# micromouse_v2.net
KiCad netlist of a schematic drawn in EAGLE
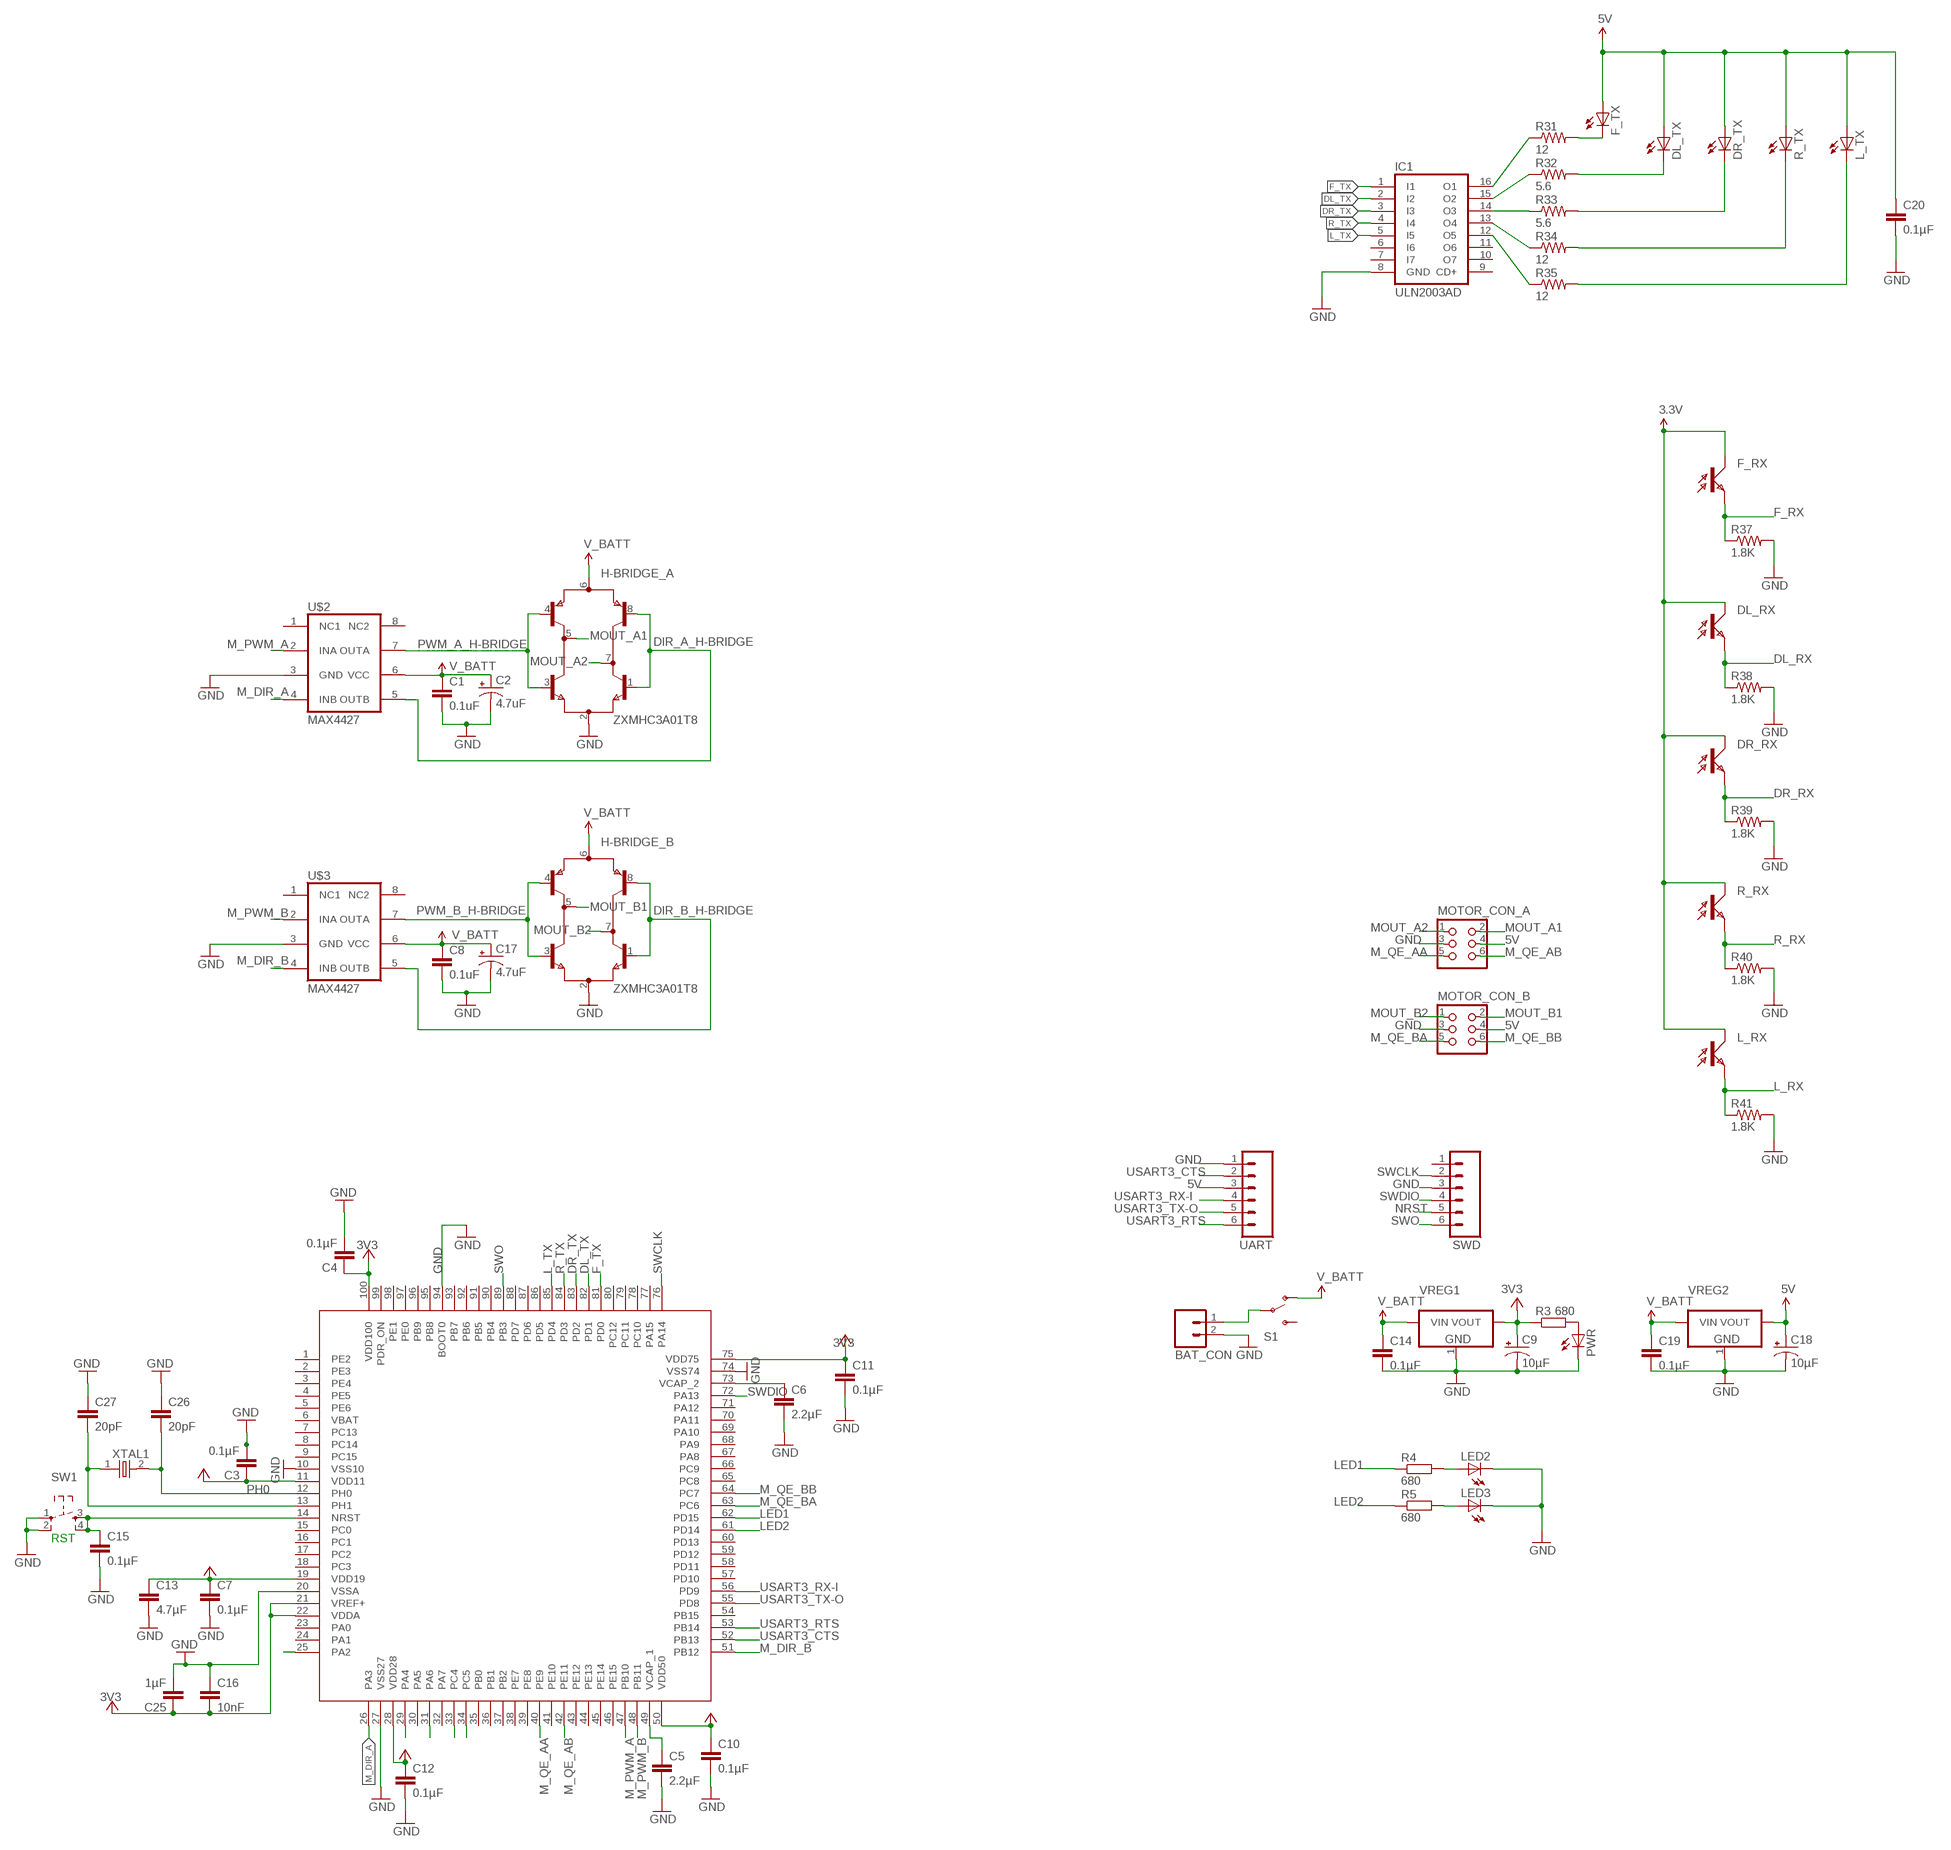
[diagram p0: schematic, sheet 1]

(export (version "E")
  (design (tool "Eeschema 10.0.6"))
  (components
    (comp (ref "BAT_CON")
      (value "M02LOCK_LONGPADS")
      (footprint "eagle-import:1X02_LOCK_LONGPADS")
      (libsource (lib "eagle-import") (part "M02LOCK_LONGPADS"))
    )
    (comp (ref "C1")
      (value "0.1uF")
      (footprint "eagle-import:1206")
      (libsource (lib "eagle-import") (part "CAP1206"))
    )
    (comp (ref "C2")
      (value "4.7uF")
      (footprint "eagle-import:EIA3216-KIT")
      (libsource (lib "eagle-import") (part "CAP_POL1206-KIT"))
    )
    (comp (ref "C3")
      (value "0.1µF")
      (footprint "eagle-import:1206")
      (libsource (lib "eagle-import") (part "CAP1206"))
    )
    (comp (ref "C4")
      (value "0.1µF")
      (footprint "eagle-import:1206")
      (libsource (lib "eagle-import") (part "CAP1206"))
    )
    (comp (ref "C5")
      (value "2.2µF")
      (footprint "eagle-import:1206")
      (libsource (lib "eagle-import") (part "CAP1206"))
    )
    (comp (ref "C6")
      (value "2.2µF")
      (footprint "eagle-import:1206")
      (libsource (lib "eagle-import") (part "CAP1206"))
    )
    (comp (ref "C7")
      (value "0.1µF")
      (footprint "eagle-import:1206")
      (libsource (lib "eagle-import") (part "CAP1206"))
    )
    (comp (ref "C8")
      (value "0.1uF")
      (footprint "eagle-import:1206")
      (libsource (lib "eagle-import") (part "CAP1206"))
    )
    (comp (ref "C9")
      (value "10µF")
      (footprint "eagle-import:EIA3216")
      (libsource (lib "eagle-import") (part "CAP_POL1206"))
    )
    (comp (ref "C10")
      (value "0.1µF")
      (footprint "eagle-import:1206")
      (libsource (lib "eagle-import") (part "CAP1206"))
    )
    (comp (ref "C11")
      (value "0.1µF")
      (footprint "eagle-import:1206")
      (libsource (lib "eagle-import") (part "CAP1206"))
    )
    (comp (ref "C12")
      (value "0.1µF")
      (footprint "eagle-import:1206")
      (libsource (lib "eagle-import") (part "CAP1206"))
    )
    (comp (ref "C13")
      (value "4.7µF")
      (footprint "eagle-import:1206")
      (libsource (lib "eagle-import") (part "CAP1206"))
    )
    (comp (ref "C14")
      (value "0.1µF")
      (footprint "eagle-import:1206")
      (libsource (lib "eagle-import") (part "CAP1206"))
    )
    (comp (ref "C15")
      (value "0.1µF")
      (footprint "eagle-import:1206")
      (libsource (lib "eagle-import") (part "CAP1206"))
    )
    (comp (ref "C16")
      (value "10nF")
      (footprint "eagle-import:1206")
      (libsource (lib "eagle-import") (part "CAP1206"))
    )
    (comp (ref "C17")
      (value "4.7uF")
      (footprint "eagle-import:EIA3216-KIT")
      (libsource (lib "eagle-import") (part "CAP_POL1206-KIT"))
    )
    (comp (ref "C18")
      (value "10µF")
      (footprint "eagle-import:EIA3216")
      (libsource (lib "eagle-import") (part "CAP_POL1206"))
    )
    (comp (ref "C19")
      (value "0.1µF")
      (footprint "eagle-import:1206")
      (libsource (lib "eagle-import") (part "CAP1206"))
    )
    (comp (ref "C20")
      (value "0.1µF")
      (footprint "eagle-import:1206")
      (libsource (lib "eagle-import") (part "CAP1206"))
    )
    (comp (ref "C25")
      (value "1µF")
      (footprint "eagle-import:1206")
      (libsource (lib "eagle-import") (part "CAP1206"))
    )
    (comp (ref "C26")
      (value "20pF")
      (footprint "eagle-import:1206")
      (libsource (lib "eagle-import") (part "CAP1206"))
    )
    (comp (ref "C27")
      (value "20pF")
      (footprint "eagle-import:1206")
      (libsource (lib "eagle-import") (part "CAP1206"))
    )
    (comp (ref "DL_RX")
      (value "BPX81")
      (footprint "eagle-import:BPX81")
      (libsource (lib "eagle-import") (part "BPX81"))
    )
    (comp (ref "DL_TX")
      (value "SFH482")
      (footprint "eagle-import:SFH482")
      (libsource (lib "eagle-import") (part "SFH482"))
    )
    (comp (ref "DR_RX")
      (value "BPX81")
      (footprint "eagle-import:BPX81")
      (libsource (lib "eagle-import") (part "BPX81"))
    )
    (comp (ref "DR_TX")
      (value "SFH482")
      (footprint "eagle-import:SFH482")
      (libsource (lib "eagle-import") (part "SFH482"))
    )
    (comp (ref "F_RX")
      (value "BPX81")
      (footprint "eagle-import:BPX81")
      (libsource (lib "eagle-import") (part "BPX81"))
    )
    (comp (ref "F_TX")
      (value "SFH482")
      (footprint "eagle-import:SFH482")
      (libsource (lib "eagle-import") (part "SFH482"))
    )
    (comp (ref "H-BRIDGE_A")
      (value "ZXMHC3A01T8")
      (footprint "eagle-import:SM8")
      (libsource (lib "eagle-import") (part "H-BRIDGE"))
    )
    (comp (ref "H-BRIDGE_B")
      (value "ZXMHC3A01T8")
      (footprint "eagle-import:SM8")
      (libsource (lib "eagle-import") (part "H-BRIDGE"))
    )
    (comp (ref "IC1")
      (value "ULN2003AD")
      (footprint "eagle-import:SO16")
      (libsource (lib "eagle-import") (part "ULN2003AD"))
    )
    (comp (ref "LED2")
      (value "LED-FKIT-1206")
      (footprint "eagle-import:FKIT-LED-1206")
      (libsource (lib "eagle-import") (part "LED-FKIT-1206"))
    )
    (comp (ref "LED3")
      (value "LED-FKIT-1206")
      (footprint "eagle-import:FKIT-LED-1206")
      (libsource (lib "eagle-import") (part "LED-FKIT-1206"))
    )
    (comp (ref "L_RX")
      (value "BPX81")
      (footprint "eagle-import:BPX81")
      (libsource (lib "eagle-import") (part "BPX81"))
    )
    (comp (ref "L_TX")
      (value "SFH482")
      (footprint "eagle-import:SFH482")
      (libsource (lib "eagle-import") (part "SFH482"))
    )
    (comp (ref "MOTOR_CON_A")
      (value "CON_HEADER_2X03-PTH")
      (footprint "eagle-import:M2X3")
      (libsource (lib "eagle-import") (part "CON_HEADER_2X03-PTH"))
    )
    (comp (ref "MOTOR_CON_B")
      (value "CON_HEADER_2X03-PTH")
      (footprint "eagle-import:M2X3")
      (libsource (lib "eagle-import") (part "CON_HEADER_2X03-PTH"))
    )
    (comp (ref "PWR")
      (value "LED-FKIT-1206")
      (footprint "eagle-import:FKIT-LED-1206")
      (libsource (lib "eagle-import") (part "LED-FKIT-1206"))
    )
    (comp (ref "R3")
      (value "680")
      (footprint "eagle-import:R1206")
      (libsource (lib "eagle-import") (part "RESISTOR-1206"))
    )
    (comp (ref "R4")
      (value "680")
      (footprint "eagle-import:R1206")
      (libsource (lib "eagle-import") (part "RESISTOR-1206"))
    )
    (comp (ref "R5")
      (value "680")
      (footprint "eagle-import:R1206")
      (libsource (lib "eagle-import") (part "RESISTOR-1206"))
    )
    (comp (ref "R31")
      (value "12")
      (footprint "eagle-import:1206")
      (libsource (lib "eagle-import") (part "RESISTOR1206"))
    )
    (comp (ref "R32")
      (value "5.6")
      (footprint "eagle-import:1206")
      (libsource (lib "eagle-import") (part "RESISTOR1206"))
    )
    (comp (ref "R33")
      (value "5.6")
      (footprint "eagle-import:1206")
      (libsource (lib "eagle-import") (part "RESISTOR1206"))
    )
    (comp (ref "R34")
      (value "12")
      (footprint "eagle-import:1206")
      (libsource (lib "eagle-import") (part "RESISTOR1206"))
    )
    (comp (ref "R35")
      (value "12")
      (footprint "eagle-import:1206")
      (libsource (lib "eagle-import") (part "RESISTOR1206"))
    )
    (comp (ref "R37")
      (value "1.8K")
      (footprint "eagle-import:1206")
      (libsource (lib "eagle-import") (part "RESISTOR1206"))
    )
    (comp (ref "R38")
      (value "1.8K")
      (footprint "eagle-import:1206")
      (libsource (lib "eagle-import") (part "RESISTOR1206"))
    )
    (comp (ref "R39")
      (value "1.8K")
      (footprint "eagle-import:1206")
      (libsource (lib "eagle-import") (part "RESISTOR1206"))
    )
    (comp (ref "R40")
      (value "1.8K")
      (footprint "eagle-import:1206")
      (libsource (lib "eagle-import") (part "RESISTOR1206"))
    )
    (comp (ref "R41")
      (value "1.8K")
      (footprint "eagle-import:1206")
      (libsource (lib "eagle-import") (part "RESISTOR1206"))
    )
    (comp (ref "R_RX")
      (value "BPX81")
      (footprint "eagle-import:BPX81")
      (libsource (lib "eagle-import") (part "BPX81"))
    )
    (comp (ref "R_TX")
      (value "SFH482")
      (footprint "eagle-import:SFH482")
      (libsource (lib "eagle-import") (part "SFH482"))
    )
    (comp (ref "S1")
      (value "SWITCH-SPDTPTH")
      (footprint "eagle-import:SWITCH-SPDT")
      (libsource (lib "eagle-import") (part "SWITCH-SPDTPTH"))
    )
    (comp (ref "SW1")
      (value "SW_TACT_4P")
      (footprint "eagle-import:SW_TACT_SMALL")
      (libsource (lib "eagle-import") (part "SW_TACT_4P"))
    )
    (comp (ref "SWD")
      (value "M06LOCK")
      (footprint "eagle-import:1X06_LOCK")
      (libsource (lib "eagle-import") (part "M06LOCK"))
    )
    (comp (ref "U$1")
      (value "STM32F40X_QFP_PACKAGE")
      (footprint "eagle-import:TQFP-100-14X14MM")
      (libsource (lib "eagle-import") (part "STM32F40X_QFP_PACKAGE"))
    )
    (comp (ref "U$2")
      (value "MAX4427")
      (footprint "eagle-import:SO08")
      (libsource (lib "eagle-import") (part "MAX4427"))
    )
    (comp (ref "U$3")
      (value "MAX4427")
      (footprint "eagle-import:SO08")
      (libsource (lib "eagle-import") (part "MAX4427"))
    )
    (comp (ref "UART")
      (value "M06LOCK")
      (footprint "eagle-import:1X06_LOCK")
      (libsource (lib "eagle-import") (part "M06LOCK"))
    )
    (comp (ref "VREG1")
      (value "VREG_3PINS-SOT-223")
      (footprint "eagle-import:SOT-223")
      (libsource (lib "eagle-import") (part "VREG_3PINS-SOT-223"))
    )
    (comp (ref "VREG2")
      (value "VREG_3PINS-SOT-223")
      (footprint "eagle-import:SOT-223")
      (libsource (lib "eagle-import") (part "VREG_3PINS-SOT-223"))
    )
    (comp (ref "XTAL1")
      (value "OSC-XTAL-HC-49U-SMD")
      (footprint "eagle-import:HC-49U")
      (libsource (lib "eagle-import") (part "OSC-XTAL-HC-49U-SMD"))
    )
  )
  (nets
    (net (code "1") (name "/DIR_A_H-BRIDGE") (class "Default")
      (node (ref "H-BRIDGE_A") (pin "1") (pinfunction "B3_1") (pintype "passive"))
      (node (ref "H-BRIDGE_A") (pin "8") (pinfunction "B4_8") (pintype "passive"))
      (node (ref "U$2") (pin "5") (pinfunction "OUTB_5") (pintype "power_in"))
    )
    (net (code "2") (name "/DIR_B_H-BRIDGE") (class "Default")
      (node (ref "H-BRIDGE_B") (pin "1") (pinfunction "B3_1") (pintype "passive"))
      (node (ref "H-BRIDGE_B") (pin "8") (pinfunction "B4_8") (pintype "passive"))
      (node (ref "U$3") (pin "5") (pinfunction "OUTB_5") (pintype "power_in"))
    )
    (net (code "3") (name "/DL_RX") (class "Default")
      (node (ref "DL_RX") (pin "E") (pinfunction "E_E") (pintype "passive"))
      (node (ref "R38") (pin "1") (pinfunction "1_1") (pintype "passive"))
      (node (ref "U$1") (pin "29") (pinfunction "PA4_29") (pintype "bidirectional"))
    )
    (net (code "4") (name "/DR_RX") (class "Default")
      (node (ref "DR_RX") (pin "E") (pinfunction "E_E") (pintype "passive"))
      (node (ref "R39") (pin "1") (pinfunction "1_1") (pintype "passive"))
      (node (ref "U$1") (pin "33") (pinfunction "PC4_33") (pintype "bidirectional"))
    )
    (net (code "5") (name "/F_RX") (class "Default")
      (node (ref "F_RX") (pin "E") (pinfunction "E_E") (pintype "passive"))
      (node (ref "R37") (pin "1") (pinfunction "1_1") (pintype "passive"))
      (node (ref "U$1") (pin "31") (pinfunction "PA6_31") (pintype "bidirectional"))
    )
    (net (code "6") (name "/LED1") (class "Default")
      (node (ref "R4") (pin "1") (pinfunction "1_1") (pintype "passive"))
      (node (ref "U$1") (pin "62") (pinfunction "PD15_62") (pintype "bidirectional"))
    )
    (net (code "7") (name "/LED2") (class "Default")
      (node (ref "R5") (pin "1") (pinfunction "1_1") (pintype "passive"))
      (node (ref "U$1") (pin "61") (pinfunction "PD14_61") (pintype "bidirectional"))
    )
    (net (code "8") (name "/L_RX") (class "Default")
      (node (ref "L_RX") (pin "E") (pinfunction "E_E") (pintype "passive"))
      (node (ref "R41") (pin "1") (pinfunction "1_1") (pintype "passive"))
      (node (ref "U$1") (pin "25") (pinfunction "PA2_25") (pintype "bidirectional"))
    )
    (net (code "9") (name "/MOUT_A1") (class "Default")
      (node (ref "H-BRIDGE_A") (pin "5") (pinfunction "C1C2_5") (pintype "passive"))
      (node (ref "MOTOR_CON_A") (pin "2") (pinfunction "2_2") (pintype "passive"))
    )
    (net (code "10") (name "/MOUT_A2") (class "Default")
      (node (ref "H-BRIDGE_A") (pin "7") (pinfunction "C3C4_7") (pintype "passive"))
      (node (ref "MOTOR_CON_A") (pin "1") (pinfunction "1_1") (pintype "passive"))
    )
    (net (code "11") (name "/MOUT_B1") (class "Default")
      (node (ref "H-BRIDGE_B") (pin "5") (pinfunction "C1C2_5") (pintype "passive"))
      (node (ref "MOTOR_CON_B") (pin "2") (pinfunction "2_2") (pintype "passive"))
    )
    (net (code "12") (name "/MOUT_B2") (class "Default")
      (node (ref "H-BRIDGE_B") (pin "7") (pinfunction "C3C4_7") (pintype "passive"))
      (node (ref "MOTOR_CON_B") (pin "1") (pinfunction "1_1") (pintype "passive"))
    )
    (net (code "13") (name "/M_DIR_B") (class "Default")
      (node (ref "U$1") (pin "51") (pinfunction "PB12_51") (pintype "bidirectional"))
      (node (ref "U$3") (pin "4") (pinfunction "INB_4") (pintype "passive"))
    )
    (net (code "14") (name "/M_PWM_A") (class "Default")
      (node (ref "U$1") (pin "47") (pinfunction "PB10_47") (pintype "bidirectional"))
      (node (ref "U$2") (pin "2") (pinfunction "INA_2") (pintype "passive"))
    )
    (net (code "15") (name "/M_PWM_B") (class "Default")
      (node (ref "U$1") (pin "48") (pinfunction "PB11_48") (pintype "bidirectional"))
      (node (ref "U$3") (pin "2") (pinfunction "INA_2") (pintype "passive"))
    )
    (net (code "16") (name "/M_QE_AA") (class "Default")
      (node (ref "MOTOR_CON_A") (pin "5") (pinfunction "5_5") (pintype "passive"))
      (node (ref "U$1") (pin "40") (pinfunction "PE9_40") (pintype "bidirectional"))
    )
    (net (code "17") (name "/M_QE_AB") (class "Default")
      (node (ref "MOTOR_CON_A") (pin "6") (pinfunction "6_6") (pintype "passive"))
      (node (ref "U$1") (pin "42") (pinfunction "PE11_42") (pintype "bidirectional"))
    )
    (net (code "18") (name "/M_QE_BA") (class "Default")
      (node (ref "MOTOR_CON_B") (pin "5") (pinfunction "5_5") (pintype "passive"))
      (node (ref "U$1") (pin "63") (pinfunction "PC6_63") (pintype "bidirectional"))
    )
    (net (code "19") (name "/M_QE_BB") (class "Default")
      (node (ref "MOTOR_CON_B") (pin "6") (pinfunction "6_6") (pintype "passive"))
      (node (ref "U$1") (pin "64") (pinfunction "PC7_64") (pintype "bidirectional"))
    )
    (net (code "20") (name "/NRST") (class "Default")
      (node (ref "C15") (pin "1") (pinfunction "1_1") (pintype "passive"))
      (node (ref "SW1") (pin "3") (pinfunction "3_3") (pintype "passive"))
      (node (ref "SW1") (pin "4") (pinfunction "4_4") (pintype "passive"))
      (node (ref "SWD") (pin "5") (pinfunction "5_5") (pintype "passive"))
      (node (ref "U$1") (pin "14") (pinfunction "NRST_14") (pintype "bidirectional"))
    )
    (net (code "21") (name "/PH0") (class "Default")
      (node (ref "C26") (pin "2") (pinfunction "2_2") (pintype "passive"))
      (node (ref "U$1") (pin "12") (pinfunction "PH0_12") (pintype "bidirectional"))
      (node (ref "XTAL1") (pin "2") (pinfunction "2_2") (pintype "passive"))
    )
    (net (code "22") (name "/PWM_A_H-BRIDGE") (class "Default")
      (node (ref "H-BRIDGE_A") (pin "3") (pinfunction "B2_3") (pintype "passive"))
      (node (ref "H-BRIDGE_A") (pin "4") (pinfunction "B1_4") (pintype "passive"))
      (node (ref "U$2") (pin "7") (pinfunction "OUTA_7") (pintype "output"))
    )
    (net (code "23") (name "/PWM_B_H-BRIDGE") (class "Default")
      (node (ref "H-BRIDGE_B") (pin "3") (pinfunction "B2_3") (pintype "passive"))
      (node (ref "H-BRIDGE_B") (pin "4") (pinfunction "B1_4") (pintype "passive"))
      (node (ref "U$3") (pin "7") (pinfunction "OUTA_7") (pintype "output"))
    )
    (net (code "24") (name "/R_RX") (class "Default")
      (node (ref "R40") (pin "1") (pinfunction "1_1") (pintype "passive"))
      (node (ref "R_RX") (pin "E") (pinfunction "E_E") (pintype "passive"))
      (node (ref "U$1") (pin "34") (pinfunction "PC5_34") (pintype "bidirectional"))
    )
    (net (code "25") (name "/SWCLK") (class "Default")
      (node (ref "SWD") (pin "2") (pinfunction "2_2") (pintype "passive"))
      (node (ref "U$1") (pin "76") (pinfunction "PA14_76") (pintype "bidirectional"))
    )
    (net (code "26") (name "/SWDIO") (class "Default")
      (node (ref "SWD") (pin "4") (pinfunction "4_4") (pintype "passive"))
      (node (ref "U$1") (pin "72") (pinfunction "PA13_72") (pintype "bidirectional"))
    )
    (net (code "27") (name "/SWO") (class "Default")
      (node (ref "SWD") (pin "6") (pinfunction "6_6") (pintype "passive"))
      (node (ref "U$1") (pin "89") (pinfunction "PB3_89") (pintype "bidirectional"))
    )
    (net (code "28") (name "/USART3_CTS") (class "Default")
      (node (ref "U$1") (pin "52") (pinfunction "PB13_52") (pintype "bidirectional"))
      (node (ref "UART") (pin "2") (pinfunction "2_2") (pintype "passive"))
    )
    (net (code "29") (name "/USART3_RTS") (class "Default")
      (node (ref "U$1") (pin "53") (pinfunction "PB14_53") (pintype "bidirectional"))
      (node (ref "UART") (pin "6") (pinfunction "6_6") (pintype "passive"))
    )
    (net (code "30") (name "/USART3_RX-I") (class "Default")
      (node (ref "U$1") (pin "56") (pinfunction "PD9_56") (pintype "bidirectional"))
      (node (ref "UART") (pin "4") (pinfunction "4_4") (pintype "passive"))
    )
    (net (code "31") (name "/USART3_TX-O") (class "Default")
      (node (ref "U$1") (pin "55") (pinfunction "PD8_55") (pintype "bidirectional"))
      (node (ref "UART") (pin "5") (pinfunction "5_5") (pintype "passive"))
    )
    (net (code "32") (name "3.3V") (class "Default")
      (node (ref "DL_RX") (pin "C") (pinfunction "C_C") (pintype "passive"))
      (node (ref "DR_RX") (pin "C") (pinfunction "C_C") (pintype "passive"))
      (node (ref "F_RX") (pin "C") (pinfunction "C_C") (pintype "passive"))
      (node (ref "L_RX") (pin "C") (pinfunction "C_C") (pintype "passive"))
      (node (ref "R_RX") (pin "C") (pinfunction "C_C") (pintype "passive"))
    )
    (net (code "33") (name "5V") (class "Default")
      (node (ref "C18") (pin "A") (pinfunction "+_A") (pintype "passive"))
      (node (ref "C20") (pin "1") (pinfunction "1_1") (pintype "passive"))
      (node (ref "DL_TX") (pin "A") (pinfunction "A_A") (pintype "passive"))
      (node (ref "DR_TX") (pin "A") (pinfunction "A_A") (pintype "passive"))
      (node (ref "F_TX") (pin "A") (pinfunction "A_A") (pintype "passive"))
      (node (ref "L_TX") (pin "A") (pinfunction "A_A") (pintype "passive"))
      (node (ref "MOTOR_CON_A") (pin "4") (pinfunction "4_4") (pintype "passive"))
      (node (ref "MOTOR_CON_B") (pin "4") (pinfunction "4_4") (pintype "passive"))
      (node (ref "R_TX") (pin "A") (pinfunction "A_A") (pintype "passive"))
      (node (ref "UART") (pin "3") (pinfunction "3_3") (pintype "passive"))
      (node (ref "VREG2") (pin "2") (pinfunction "VOUT_2") (pintype "bidirectional"))
    )
    (net (code "34") (name "DL_TX") (class "Default")
      (node (ref "IC1") (pin "2") (pinfunction "I2_2") (pintype "input"))
      (node (ref "U$1") (pin "82") (pinfunction "PD1_82") (pintype "bidirectional"))
    )
    (net (code "35") (name "DR_TX") (class "Default")
      (node (ref "IC1") (pin "3") (pinfunction "I3_3") (pintype "input"))
      (node (ref "U$1") (pin "83") (pinfunction "PD2_83") (pintype "bidirectional"))
    )
    (net (code "36") (name "F_TX") (class "Default")
      (node (ref "IC1") (pin "1") (pinfunction "I1_1") (pintype "input"))
      (node (ref "U$1") (pin "81") (pinfunction "PD0_81") (pintype "bidirectional"))
    )
    (net (code "37") (name "GND") (class "Default")
      (node (ref "BAT_CON") (pin "2") (pinfunction "2_2") (pintype "passive"))
      (node (ref "C1") (pin "2") (pinfunction "2_2") (pintype "passive"))
      (node (ref "C10") (pin "2") (pinfunction "2_2") (pintype "passive"))
      (node (ref "C11") (pin "2") (pinfunction "2_2") (pintype "passive"))
      (node (ref "C12") (pin "2") (pinfunction "2_2") (pintype "passive"))
      (node (ref "C13") (pin "2") (pinfunction "2_2") (pintype "passive"))
      (node (ref "C14") (pin "2") (pinfunction "2_2") (pintype "passive"))
      (node (ref "C15") (pin "2") (pinfunction "2_2") (pintype "passive"))
      (node (ref "C16") (pin "1") (pinfunction "1_1") (pintype "passive"))
      (node (ref "C17") (pin "C") (pinfunction "-_C") (pintype "passive"))
      (node (ref "C18") (pin "C") (pinfunction "-_C") (pintype "passive"))
      (node (ref "C19") (pin "2") (pinfunction "2_2") (pintype "passive"))
      (node (ref "C2") (pin "C") (pinfunction "-_C") (pintype "passive"))
      (node (ref "C20") (pin "2") (pinfunction "2_2") (pintype "passive"))
      (node (ref "C25") (pin "2") (pinfunction "2_2") (pintype "passive"))
      (node (ref "C26") (pin "1") (pinfunction "1_1") (pintype "passive"))
      (node (ref "C27") (pin "1") (pinfunction "1_1") (pintype "passive"))
      (node (ref "C3") (pin "2") (pinfunction "2_2") (pintype "passive"))
      (node (ref "C4") (pin "2") (pinfunction "2_2") (pintype "passive"))
      (node (ref "C5") (pin "2") (pinfunction "2_2") (pintype "passive"))
      (node (ref "C6") (pin "2") (pinfunction "2_2") (pintype "passive"))
      (node (ref "C7") (pin "2") (pinfunction "2_2") (pintype "passive"))
      (node (ref "C8") (pin "2") (pinfunction "2_2") (pintype "passive"))
      (node (ref "C9") (pin "C") (pinfunction "-_C") (pintype "passive"))
      (node (ref "H-BRIDGE_A") (pin "2") (pinfunction "E2E3_2") (pintype "passive"))
      (node (ref "H-BRIDGE_B") (pin "2") (pinfunction "E2E3_2") (pintype "passive"))
      (node (ref "IC1") (pin "8") (pinfunction "GND_8") (pintype "power_in"))
      (node (ref "LED2") (pin "C") (pinfunction "C_C") (pintype "passive"))
      (node (ref "LED3") (pin "C") (pinfunction "C_C") (pintype "passive"))
      (node (ref "MOTOR_CON_A") (pin "3") (pinfunction "3_3") (pintype "passive"))
      (node (ref "MOTOR_CON_B") (pin "3") (pinfunction "3_3") (pintype "passive"))
      (node (ref "PWR") (pin "C") (pinfunction "C_C") (pintype "passive"))
      (node (ref "R37") (pin "2") (pinfunction "2_2") (pintype "passive"))
      (node (ref "R38") (pin "2") (pinfunction "2_2") (pintype "passive"))
      (node (ref "R39") (pin "2") (pinfunction "2_2") (pintype "passive"))
      (node (ref "R40") (pin "2") (pinfunction "2_2") (pintype "passive"))
      (node (ref "R41") (pin "2") (pinfunction "2_2") (pintype "passive"))
      (node (ref "SW1") (pin "1") (pinfunction "1_1") (pintype "passive"))
      (node (ref "SW1") (pin "2") (pinfunction "2_2") (pintype "passive"))
      (node (ref "SWD") (pin "3") (pinfunction "3_3") (pintype "passive"))
      (node (ref "U$1") (pin "10") (pinfunction "VSS10_10") (pintype "bidirectional"))
      (node (ref "U$1") (pin "20") (pinfunction "VSSA_20") (pintype "bidirectional"))
      (node (ref "U$1") (pin "27") (pinfunction "VSS27_27") (pintype "bidirectional"))
      (node (ref "U$1") (pin "74") (pinfunction "VSS74_74") (pintype "bidirectional"))
      (node (ref "U$1") (pin "94") (pinfunction "BOOT0_94") (pintype "bidirectional"))
      (node (ref "U$2") (pin "3") (pinfunction "GND_3") (pintype "passive"))
      (node (ref "U$3") (pin "3") (pinfunction "GND_3") (pintype "passive"))
      (node (ref "UART") (pin "1") (pinfunction "1_1") (pintype "passive"))
      (node (ref "VREG1") (pin "1") (pinfunction "GND_1") (pintype "bidirectional"))
      (node (ref "VREG2") (pin "1") (pinfunction "GND_1") (pintype "bidirectional"))
    )
    (net (code "38") (name "L_TX") (class "Default")
      (node (ref "IC1") (pin "5") (pinfunction "I5_5") (pintype "input"))
      (node (ref "U$1") (pin "85") (pinfunction "PD4_85") (pintype "bidirectional"))
    )
    (net (code "39") (name "M_DIR_A") (class "Default")
      (node (ref "U$1") (pin "26") (pinfunction "PA3_26") (pintype "bidirectional"))
      (node (ref "U$2") (pin "4") (pinfunction "INB_4") (pintype "passive"))
    )
    (net (code "40") (name "Net-(DL_TX-C)") (class "Default")
      (node (ref "DL_TX") (pin "K") (pinfunction "C_K") (pintype "passive"))
      (node (ref "R32") (pin "2") (pinfunction "2_2") (pintype "passive"))
    )
    (net (code "41") (name "Net-(DR_TX-C)") (class "Default")
      (node (ref "DR_TX") (pin "K") (pinfunction "C_K") (pintype "passive"))
      (node (ref "R33") (pin "2") (pinfunction "2_2") (pintype "passive"))
    )
    (net (code "42") (name "Net-(F_TX-C)") (class "Default")
      (node (ref "F_TX") (pin "K") (pinfunction "C_K") (pintype "passive"))
      (node (ref "R31") (pin "2") (pinfunction "2_2") (pintype "passive"))
    )
    (net (code "43") (name "Net-(IC1-O1)") (class "Default")
      (node (ref "IC1") (pin "16") (pinfunction "O1_16") (pintype "open_collector"))
      (node (ref "R31") (pin "1") (pinfunction "1_1") (pintype "passive"))
    )
    (net (code "44") (name "Net-(IC1-O2)") (class "Default")
      (node (ref "IC1") (pin "15") (pinfunction "O2_15") (pintype "open_collector"))
      (node (ref "R32") (pin "1") (pinfunction "1_1") (pintype "passive"))
    )
    (net (code "45") (name "Net-(IC1-O3)") (class "Default")
      (node (ref "IC1") (pin "14") (pinfunction "O3_14") (pintype "open_collector"))
      (node (ref "R33") (pin "1") (pinfunction "1_1") (pintype "passive"))
    )
    (net (code "46") (name "Net-(IC1-O4)") (class "Default")
      (node (ref "IC1") (pin "13") (pinfunction "O4_13") (pintype "open_collector"))
      (node (ref "R34") (pin "1") (pinfunction "1_1") (pintype "passive"))
    )
    (net (code "47") (name "Net-(IC1-O5)") (class "Default")
      (node (ref "IC1") (pin "12") (pinfunction "O5_12") (pintype "open_collector"))
      (node (ref "R35") (pin "1") (pinfunction "1_1") (pintype "passive"))
    )
    (net (code "48") (name "Net-(LED2-PadA)") (class "Default")
      (node (ref "LED2") (pin "A") (pinfunction "A_A") (pintype "passive"))
      (node (ref "R4") (pin "2") (pinfunction "2_2") (pintype "passive"))
    )
    (net (code "49") (name "Net-(LED3-PadA)") (class "Default")
      (node (ref "LED3") (pin "A") (pinfunction "A_A") (pintype "passive"))
      (node (ref "R5") (pin "2") (pinfunction "2_2") (pintype "passive"))
    )
    (net (code "50") (name "Net-(L_TX-C)") (class "Default")
      (node (ref "L_TX") (pin "K") (pinfunction "C_K") (pintype "passive"))
      (node (ref "R35") (pin "2") (pinfunction "2_2") (pintype "passive"))
    )
    (net (code "51") (name "Net-(PWR-PadA)") (class "Default")
      (node (ref "PWR") (pin "A") (pinfunction "A_A") (pintype "passive"))
      (node (ref "R3") (pin "2") (pinfunction "2_2") (pintype "passive"))
    )
    (net (code "52") (name "Net-(R_TX-C)") (class "Default")
      (node (ref "R34") (pin "2") (pinfunction "2_2") (pintype "passive"))
      (node (ref "R_TX") (pin "K") (pinfunction "C_K") (pintype "passive"))
    )
    (net (code "53") (name "Net-(S1-P)") (class "Default")
      (node (ref "BAT_CON") (pin "1") (pinfunction "1_1") (pintype "passive"))
      (node (ref "S1") (pin "2") (pinfunction "P_2") (pintype "passive"))
    )
    (net (code "54") (name "Net-(U$1-PH1)") (class "Default")
      (node (ref "C27") (pin "2") (pinfunction "2_2") (pintype "passive"))
      (node (ref "U$1") (pin "13") (pinfunction "PH1_13") (pintype "bidirectional"))
      (node (ref "XTAL1") (pin "1") (pinfunction "1_1") (pintype "passive"))
    )
    (net (code "55") (name "Net-(U$1-VCAP_1)") (class "Default")
      (node (ref "C5") (pin "1") (pinfunction "1_1") (pintype "passive"))
      (node (ref "U$1") (pin "49") (pinfunction "VCAP_1_49") (pintype "bidirectional"))
    )
    (net (code "56") (name "Net-(U$1-VCAP_2)") (class "Default")
      (node (ref "C6") (pin "1") (pinfunction "1_1") (pintype "passive"))
      (node (ref "U$1") (pin "73") (pinfunction "VCAP_2_73") (pintype "bidirectional"))
    )
    (net (code "57") (name "R_TX") (class "Default")
      (node (ref "IC1") (pin "4") (pinfunction "I4_4") (pintype "input"))
      (node (ref "U$1") (pin "84") (pinfunction "PD3_84") (pintype "bidirectional"))
    )
    (net (code "58") (name "SUPPLY_+3V3") (class "Default")
      (node (ref "C10") (pin "1") (pinfunction "1_1") (pintype "passive"))
      (node (ref "C11") (pin "1") (pinfunction "1_1") (pintype "passive"))
      (node (ref "C12") (pin "1") (pinfunction "1_1") (pintype "passive"))
      (node (ref "C13") (pin "1") (pinfunction "1_1") (pintype "passive"))
      (node (ref "C16") (pin "2") (pinfunction "2_2") (pintype "passive"))
      (node (ref "C25") (pin "1") (pinfunction "1_1") (pintype "passive"))
      (node (ref "C3") (pin "1") (pinfunction "1_1") (pintype "passive"))
      (node (ref "C4") (pin "1") (pinfunction "1_1") (pintype "passive"))
      (node (ref "C7") (pin "1") (pinfunction "1_1") (pintype "passive"))
      (node (ref "C9") (pin "A") (pinfunction "+_A") (pintype "passive"))
      (node (ref "R3") (pin "1") (pinfunction "1_1") (pintype "passive"))
      (node (ref "U$1") (pin "100") (pinfunction "VDD100_100") (pintype "bidirectional"))
      (node (ref "U$1") (pin "11") (pinfunction "VDD11_11") (pintype "bidirectional"))
      (node (ref "U$1") (pin "19") (pinfunction "VDD19_19") (pintype "bidirectional"))
      (node (ref "U$1") (pin "21") (pinfunction "VREF+_21") (pintype "bidirectional"))
      (node (ref "U$1") (pin "22") (pinfunction "VDDA_22") (pintype "bidirectional"))
      (node (ref "U$1") (pin "28") (pinfunction "VDD28_28") (pintype "bidirectional"))
      (node (ref "U$1") (pin "50") (pinfunction "VDD50_50") (pintype "bidirectional"))
      (node (ref "U$1") (pin "75") (pinfunction "VDD75_75") (pintype "bidirectional"))
      (node (ref "VREG1") (pin "2") (pinfunction "VOUT_2") (pintype "bidirectional"))
    )
    (net (code "59") (name "V_BATT") (class "Default")
      (node (ref "C1") (pin "1") (pinfunction "1_1") (pintype "passive"))
      (node (ref "C14") (pin "1") (pinfunction "1_1") (pintype "passive"))
      (node (ref "C17") (pin "A") (pinfunction "+_A") (pintype "passive"))
      (node (ref "C19") (pin "1") (pinfunction "1_1") (pintype "passive"))
      (node (ref "C2") (pin "A") (pinfunction "+_A") (pintype "passive"))
      (node (ref "C8") (pin "1") (pinfunction "1_1") (pintype "passive"))
      (node (ref "H-BRIDGE_A") (pin "6") (pinfunction "E1E4_6") (pintype "passive"))
      (node (ref "H-BRIDGE_B") (pin "6") (pinfunction "E1E4_6") (pintype "passive"))
      (node (ref "S1") (pin "1") (pinfunction "O_1") (pintype "passive"))
      (node (ref "U$2") (pin "6") (pinfunction "VCC_6") (pintype "power_in"))
      (node (ref "U$3") (pin "6") (pinfunction "VCC_6") (pintype "power_in"))
      (node (ref "VREG1") (pin "3") (pinfunction "VIN_3") (pintype "bidirectional"))
      (node (ref "VREG2") (pin "3") (pinfunction "VIN_3") (pintype "bidirectional"))
    )
    (net (code "60") (name "unconnected-(IC1-CD+-Pad9)") (class "Default")
      (node (ref "IC1") (pin "9") (pinfunction "CD+_9") (pintype "passive"))
    )
    (net (code "61") (name "unconnected-(IC1-I6-Pad6)") (class "Default")
      (node (ref "IC1") (pin "6") (pinfunction "I6_6") (pintype "input"))
    )
    (net (code "62") (name "unconnected-(IC1-I7-Pad7)") (class "Default")
      (node (ref "IC1") (pin "7") (pinfunction "I7_7") (pintype "input"))
    )
    (net (code "63") (name "unconnected-(IC1-O6-Pad11)") (class "Default")
      (node (ref "IC1") (pin "11") (pinfunction "O6_11") (pintype "open_collector"))
    )
    (net (code "64") (name "unconnected-(IC1-O7-Pad10)") (class "Default")
      (node (ref "IC1") (pin "10") (pinfunction "O7_10") (pintype "open_collector"))
    )
    (net (code "65") (name "unconnected-(S1-S-Pad3)") (class "Default")
      (node (ref "S1") (pin "3") (pinfunction "S_3") (pintype "passive"))
    )
    (net (code "66") (name "unconnected-(SWD-Pad1)") (class "Default")
      (node (ref "SWD") (pin "1") (pinfunction "1_1") (pintype "passive"))
    )
    (net (code "67") (name "unconnected-(U$1-PA0-Pad23)") (class "Default")
      (node (ref "U$1") (pin "23") (pinfunction "PA0_23") (pintype "bidirectional"))
    )
    (net (code "68") (name "unconnected-(U$1-PA1-Pad24)") (class "Default")
      (node (ref "U$1") (pin "24") (pinfunction "PA1_24") (pintype "bidirectional"))
    )
    (net (code "69") (name "unconnected-(U$1-PA5-Pad30)") (class "Default")
      (node (ref "U$1") (pin "30") (pinfunction "PA5_30") (pintype "bidirectional"))
    )
    (net (code "70") (name "unconnected-(U$1-PA7-Pad32)") (class "Default")
      (node (ref "U$1") (pin "32") (pinfunction "PA7_32") (pintype "bidirectional"))
    )
    (net (code "71") (name "unconnected-(U$1-PA8-Pad67)") (class "Default")
      (node (ref "U$1") (pin "67") (pinfunction "PA8_67") (pintype "bidirectional"))
    )
    (net (code "72") (name "unconnected-(U$1-PA9-Pad68)") (class "Default")
      (node (ref "U$1") (pin "68") (pinfunction "PA9_68") (pintype "bidirectional"))
    )
    (net (code "73") (name "unconnected-(U$1-PA10-Pad69)") (class "Default")
      (node (ref "U$1") (pin "69") (pinfunction "PA10_69") (pintype "bidirectional"))
    )
    (net (code "74") (name "unconnected-(U$1-PA11-Pad70)") (class "Default")
      (node (ref "U$1") (pin "70") (pinfunction "PA11_70") (pintype "bidirectional"))
    )
    (net (code "75") (name "unconnected-(U$1-PA12-Pad71)") (class "Default")
      (node (ref "U$1") (pin "71") (pinfunction "PA12_71") (pintype "bidirectional"))
    )
    (net (code "76") (name "unconnected-(U$1-PA15-Pad77)") (class "Default")
      (node (ref "U$1") (pin "77") (pinfunction "PA15_77") (pintype "bidirectional"))
    )
    (net (code "77") (name "unconnected-(U$1-PB0-Pad35)") (class "Default")
      (node (ref "U$1") (pin "35") (pinfunction "PB0_35") (pintype "bidirectional"))
    )
    (net (code "78") (name "unconnected-(U$1-PB1-Pad36)") (class "Default")
      (node (ref "U$1") (pin "36") (pinfunction "PB1_36") (pintype "bidirectional"))
    )
    (net (code "79") (name "unconnected-(U$1-PB2-Pad37)") (class "Default")
      (node (ref "U$1") (pin "37") (pinfunction "PB2_37") (pintype "bidirectional"))
    )
    (net (code "80") (name "unconnected-(U$1-PB4-Pad90)") (class "Default")
      (node (ref "U$1") (pin "90") (pinfunction "PB4_90") (pintype "bidirectional"))
    )
    (net (code "81") (name "unconnected-(U$1-PB5-Pad91)") (class "Default")
      (node (ref "U$1") (pin "91") (pinfunction "PB5_91") (pintype "bidirectional"))
    )
    (net (code "82") (name "unconnected-(U$1-PB6-Pad92)") (class "Default")
      (node (ref "U$1") (pin "92") (pinfunction "PB6_92") (pintype "bidirectional"))
    )
    (net (code "83") (name "unconnected-(U$1-PB7-Pad93)") (class "Default")
      (node (ref "U$1") (pin "93") (pinfunction "PB7_93") (pintype "bidirectional"))
    )
    (net (code "84") (name "unconnected-(U$1-PB8-Pad95)") (class "Default")
      (node (ref "U$1") (pin "95") (pinfunction "PB8_95") (pintype "bidirectional"))
    )
    (net (code "85") (name "unconnected-(U$1-PB9-Pad96)") (class "Default")
      (node (ref "U$1") (pin "96") (pinfunction "PB9_96") (pintype "bidirectional"))
    )
    (net (code "86") (name "unconnected-(U$1-PB15-Pad54)") (class "Default")
      (node (ref "U$1") (pin "54") (pinfunction "PB15_54") (pintype "bidirectional"))
    )
    (net (code "87") (name "unconnected-(U$1-PC0-Pad15)") (class "Default")
      (node (ref "U$1") (pin "15") (pinfunction "PC0_15") (pintype "bidirectional"))
    )
    (net (code "88") (name "unconnected-(U$1-PC1-Pad16)") (class "Default")
      (node (ref "U$1") (pin "16") (pinfunction "PC1_16") (pintype "bidirectional"))
    )
    (net (code "89") (name "unconnected-(U$1-PC2-Pad17)") (class "Default")
      (node (ref "U$1") (pin "17") (pinfunction "PC2_17") (pintype "bidirectional"))
    )
    (net (code "90") (name "unconnected-(U$1-PC3-Pad18)") (class "Default")
      (node (ref "U$1") (pin "18") (pinfunction "PC3_18") (pintype "bidirectional"))
    )
    (net (code "91") (name "unconnected-(U$1-PC8-Pad65)") (class "Default")
      (node (ref "U$1") (pin "65") (pinfunction "PC8_65") (pintype "bidirectional"))
    )
    (net (code "92") (name "unconnected-(U$1-PC9-Pad66)") (class "Default")
      (node (ref "U$1") (pin "66") (pinfunction "PC9_66") (pintype "bidirectional"))
    )
    (net (code "93") (name "unconnected-(U$1-PC10-Pad78)") (class "Default")
      (node (ref "U$1") (pin "78") (pinfunction "PC10_78") (pintype "bidirectional"))
    )
    (net (code "94") (name "unconnected-(U$1-PC11-Pad79)") (class "Default")
      (node (ref "U$1") (pin "79") (pinfunction "PC11_79") (pintype "bidirectional"))
    )
    (net (code "95") (name "unconnected-(U$1-PC12-Pad80)") (class "Default")
      (node (ref "U$1") (pin "80") (pinfunction "PC12_80") (pintype "bidirectional"))
    )
    (net (code "96") (name "unconnected-(U$1-PC13-Pad7)") (class "Default")
      (node (ref "U$1") (pin "7") (pinfunction "PC13_7") (pintype "bidirectional"))
    )
    (net (code "97") (name "unconnected-(U$1-PC14-Pad8)") (class "Default")
      (node (ref "U$1") (pin "8") (pinfunction "PC14_8") (pintype "bidirectional"))
    )
    (net (code "98") (name "unconnected-(U$1-PC15-Pad9)") (class "Default")
      (node (ref "U$1") (pin "9") (pinfunction "PC15_9") (pintype "bidirectional"))
    )
    (net (code "99") (name "unconnected-(U$1-PD5-Pad86)") (class "Default")
      (node (ref "U$1") (pin "86") (pinfunction "PD5_86") (pintype "bidirectional"))
    )
    (net (code "100") (name "unconnected-(U$1-PD6-Pad87)") (class "Default")
      (node (ref "U$1") (pin "87") (pinfunction "PD6_87") (pintype "bidirectional"))
    )
    (net (code "101") (name "unconnected-(U$1-PD7-Pad88)") (class "Default")
      (node (ref "U$1") (pin "88") (pinfunction "PD7_88") (pintype "bidirectional"))
    )
    (net (code "102") (name "unconnected-(U$1-PD10-Pad57)") (class "Default")
      (node (ref "U$1") (pin "57") (pinfunction "PD10_57") (pintype "bidirectional"))
    )
    (net (code "103") (name "unconnected-(U$1-PD11-Pad58)") (class "Default")
      (node (ref "U$1") (pin "58") (pinfunction "PD11_58") (pintype "bidirectional"))
    )
    (net (code "104") (name "unconnected-(U$1-PD12-Pad59)") (class "Default")
      (node (ref "U$1") (pin "59") (pinfunction "PD12_59") (pintype "bidirectional"))
    )
    (net (code "105") (name "unconnected-(U$1-PD13-Pad60)") (class "Default")
      (node (ref "U$1") (pin "60") (pinfunction "PD13_60") (pintype "bidirectional"))
    )
    (net (code "106") (name "unconnected-(U$1-PDR_ON-Pad99)") (class "Default")
      (node (ref "U$1") (pin "99") (pinfunction "PDR_ON_99") (pintype "bidirectional"))
    )
    (net (code "107") (name "unconnected-(U$1-PE0-Pad97)") (class "Default")
      (node (ref "U$1") (pin "97") (pinfunction "PE0_97") (pintype "bidirectional"))
    )
    (net (code "108") (name "unconnected-(U$1-PE1-Pad98)") (class "Default")
      (node (ref "U$1") (pin "98") (pinfunction "PE1_98") (pintype "bidirectional"))
    )
    (net (code "109") (name "unconnected-(U$1-PE2-Pad1)") (class "Default")
      (node (ref "U$1") (pin "1") (pinfunction "PE2_1") (pintype "bidirectional"))
    )
    (net (code "110") (name "unconnected-(U$1-PE3-Pad2)") (class "Default")
      (node (ref "U$1") (pin "2") (pinfunction "PE3_2") (pintype "bidirectional"))
    )
    (net (code "111") (name "unconnected-(U$1-PE4-Pad3)") (class "Default")
      (node (ref "U$1") (pin "3") (pinfunction "PE4_3") (pintype "bidirectional"))
    )
    (net (code "112") (name "unconnected-(U$1-PE5-Pad4)") (class "Default")
      (node (ref "U$1") (pin "4") (pinfunction "PE5_4") (pintype "bidirectional"))
    )
    (net (code "113") (name "unconnected-(U$1-PE6-Pad5)") (class "Default")
      (node (ref "U$1") (pin "5") (pinfunction "PE6_5") (pintype "bidirectional"))
    )
    (net (code "114") (name "unconnected-(U$1-PE7-Pad38)") (class "Default")
      (node (ref "U$1") (pin "38") (pinfunction "PE7_38") (pintype "bidirectional"))
    )
    (net (code "115") (name "unconnected-(U$1-PE8-Pad39)") (class "Default")
      (node (ref "U$1") (pin "39") (pinfunction "PE8_39") (pintype "bidirectional"))
    )
    (net (code "116") (name "unconnected-(U$1-PE10-Pad41)") (class "Default")
      (node (ref "U$1") (pin "41") (pinfunction "PE10_41") (pintype "bidirectional"))
    )
    (net (code "117") (name "unconnected-(U$1-PE12-Pad43)") (class "Default")
      (node (ref "U$1") (pin "43") (pinfunction "PE12_43") (pintype "bidirectional"))
    )
    (net (code "118") (name "unconnected-(U$1-PE13-Pad44)") (class "Default")
      (node (ref "U$1") (pin "44") (pinfunction "PE13_44") (pintype "bidirectional"))
    )
    (net (code "119") (name "unconnected-(U$1-PE14-Pad45)") (class "Default")
      (node (ref "U$1") (pin "45") (pinfunction "PE14_45") (pintype "bidirectional"))
    )
    (net (code "120") (name "unconnected-(U$1-PE15-Pad46)") (class "Default")
      (node (ref "U$1") (pin "46") (pinfunction "PE15_46") (pintype "bidirectional"))
    )
    (net (code "121") (name "unconnected-(U$1-VBAT-Pad6)") (class "Default")
      (node (ref "U$1") (pin "6") (pinfunction "VBAT_6") (pintype "bidirectional"))
    )
    (net (code "122") (name "unconnected-(U$2-NC1-Pad1)") (class "Default")
      (node (ref "U$2") (pin "1") (pinfunction "NC1_1") (pintype "passive"))
    )
    (net (code "123") (name "unconnected-(U$2-NC2-Pad8)") (class "Default")
      (node (ref "U$2") (pin "8") (pinfunction "NC2_8") (pintype "output"))
    )
    (net (code "124") (name "unconnected-(U$3-NC1-Pad1)") (class "Default")
      (node (ref "U$3") (pin "1") (pinfunction "NC1_1") (pintype "passive"))
    )
    (net (code "125") (name "unconnected-(U$3-NC2-Pad8)") (class "Default")
      (node (ref "U$3") (pin "8") (pinfunction "NC2_8") (pintype "output"))
    )
  )
)
